# SparkFun_adapter-ssop8-v10.net
KiCad netlist of a schematic drawn in EAGLE
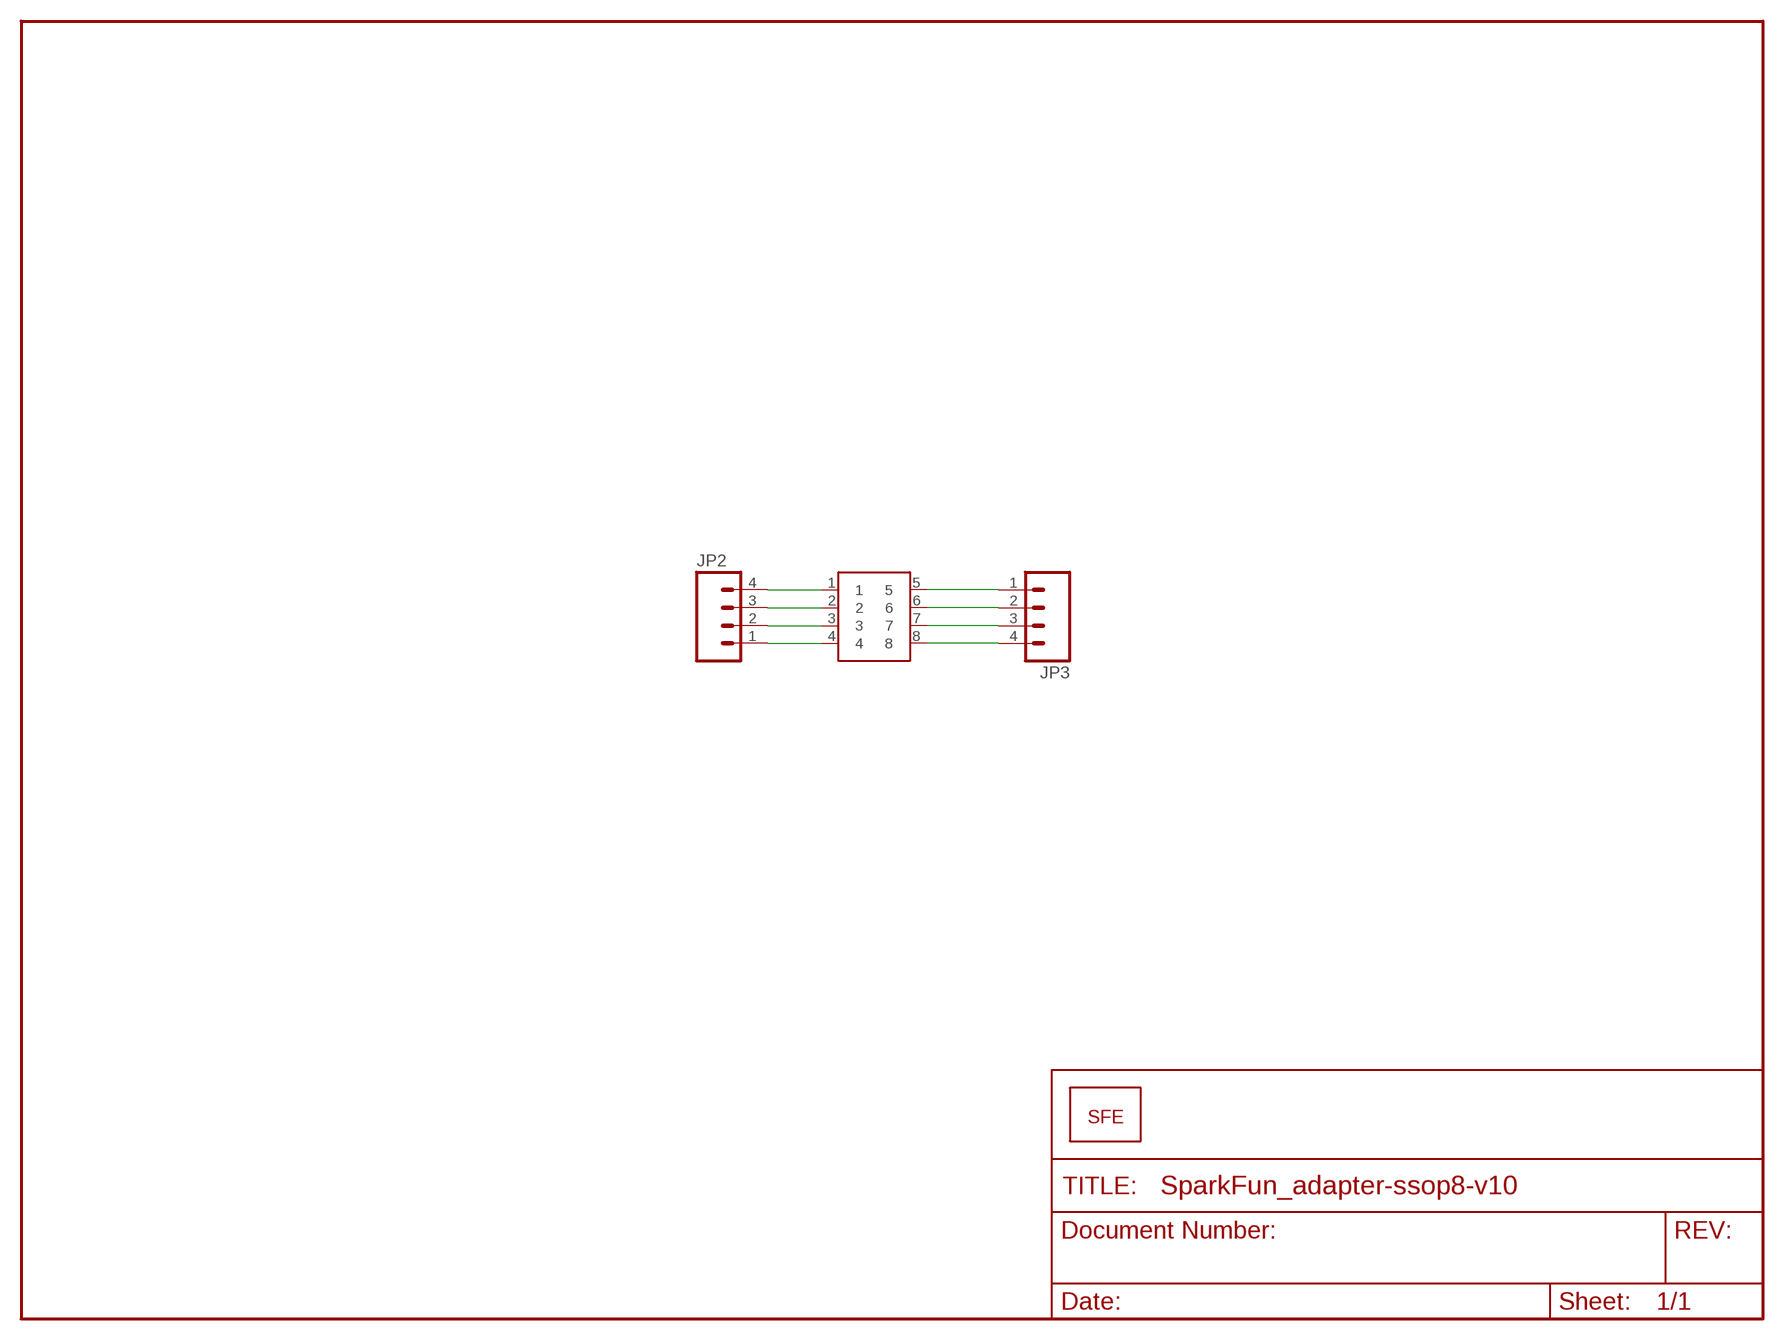
[diagram p0: schematic, sheet 1]

(export (version "E")
  (design (tool "Eeschema 10.0.6"))
  (components
    (comp (ref "JP1")
      (value "LOGO-SFESK")
      (footprint "eagle-import:SFE-LOGO-FLAME")
      (libsource (lib "eagle-import") (part "LOGO-SFESK"))
    )
    (comp (ref "JP2")
      (value "M04PTH")
      (footprint "eagle-import:1X04")
      (libsource (lib "eagle-import") (part "M04PTH"))
    )
    (comp (ref "JP3")
      (value "M04PTH")
      (footprint "eagle-import:1X04")
      (libsource (lib "eagle-import") (part "M04PTH"))
    )
    (comp (ref "U$1")
      (value "SSOP8")
      (footprint "eagle-import:SSOP8")
      (libsource (lib "eagle-import") (part "SSOP8"))
    )
  )
  (nets
    (net (code "1") (name "Net-(JP2-Pad1)") (class "Default")
      (node (ref "JP2") (pin "1") (pinfunction "1_1") (pintype "passive"))
      (node (ref "U$1") (pin "4") (pinfunction "4_4") (pintype "bidirectional"))
    )
    (net (code "2") (name "Net-(JP2-Pad2)") (class "Default")
      (node (ref "JP2") (pin "2") (pinfunction "2_2") (pintype "passive"))
      (node (ref "U$1") (pin "3") (pinfunction "3_3") (pintype "bidirectional"))
    )
    (net (code "3") (name "Net-(JP2-Pad3)") (class "Default")
      (node (ref "JP2") (pin "3") (pinfunction "3_3") (pintype "passive"))
      (node (ref "U$1") (pin "2") (pinfunction "2_2") (pintype "bidirectional"))
    )
    (net (code "4") (name "Net-(JP2-Pad4)") (class "Default")
      (node (ref "JP2") (pin "4") (pinfunction "4_4") (pintype "passive"))
      (node (ref "U$1") (pin "1") (pinfunction "1_1") (pintype "bidirectional"))
    )
    (net (code "5") (name "Net-(JP3-Pad1)") (class "Default")
      (node (ref "JP3") (pin "1") (pinfunction "1_1") (pintype "passive"))
      (node (ref "U$1") (pin "5") (pinfunction "5_5") (pintype "bidirectional"))
    )
    (net (code "6") (name "Net-(JP3-Pad2)") (class "Default")
      (node (ref "JP3") (pin "2") (pinfunction "2_2") (pintype "passive"))
      (node (ref "U$1") (pin "6") (pinfunction "6_6") (pintype "bidirectional"))
    )
    (net (code "7") (name "Net-(JP3-Pad3)") (class "Default")
      (node (ref "JP3") (pin "3") (pinfunction "3_3") (pintype "passive"))
      (node (ref "U$1") (pin "7") (pinfunction "7_7") (pintype "bidirectional"))
    )
    (net (code "8") (name "Net-(JP3-Pad4)") (class "Default")
      (node (ref "JP3") (pin "4") (pinfunction "4_4") (pintype "passive"))
      (node (ref "U$1") (pin "8") (pinfunction "8_8") (pintype "bidirectional"))
    )
  )
)
